# py32f002asop8v1.net
KiCad netlist of a schematic drawn in EasyEDA Pro
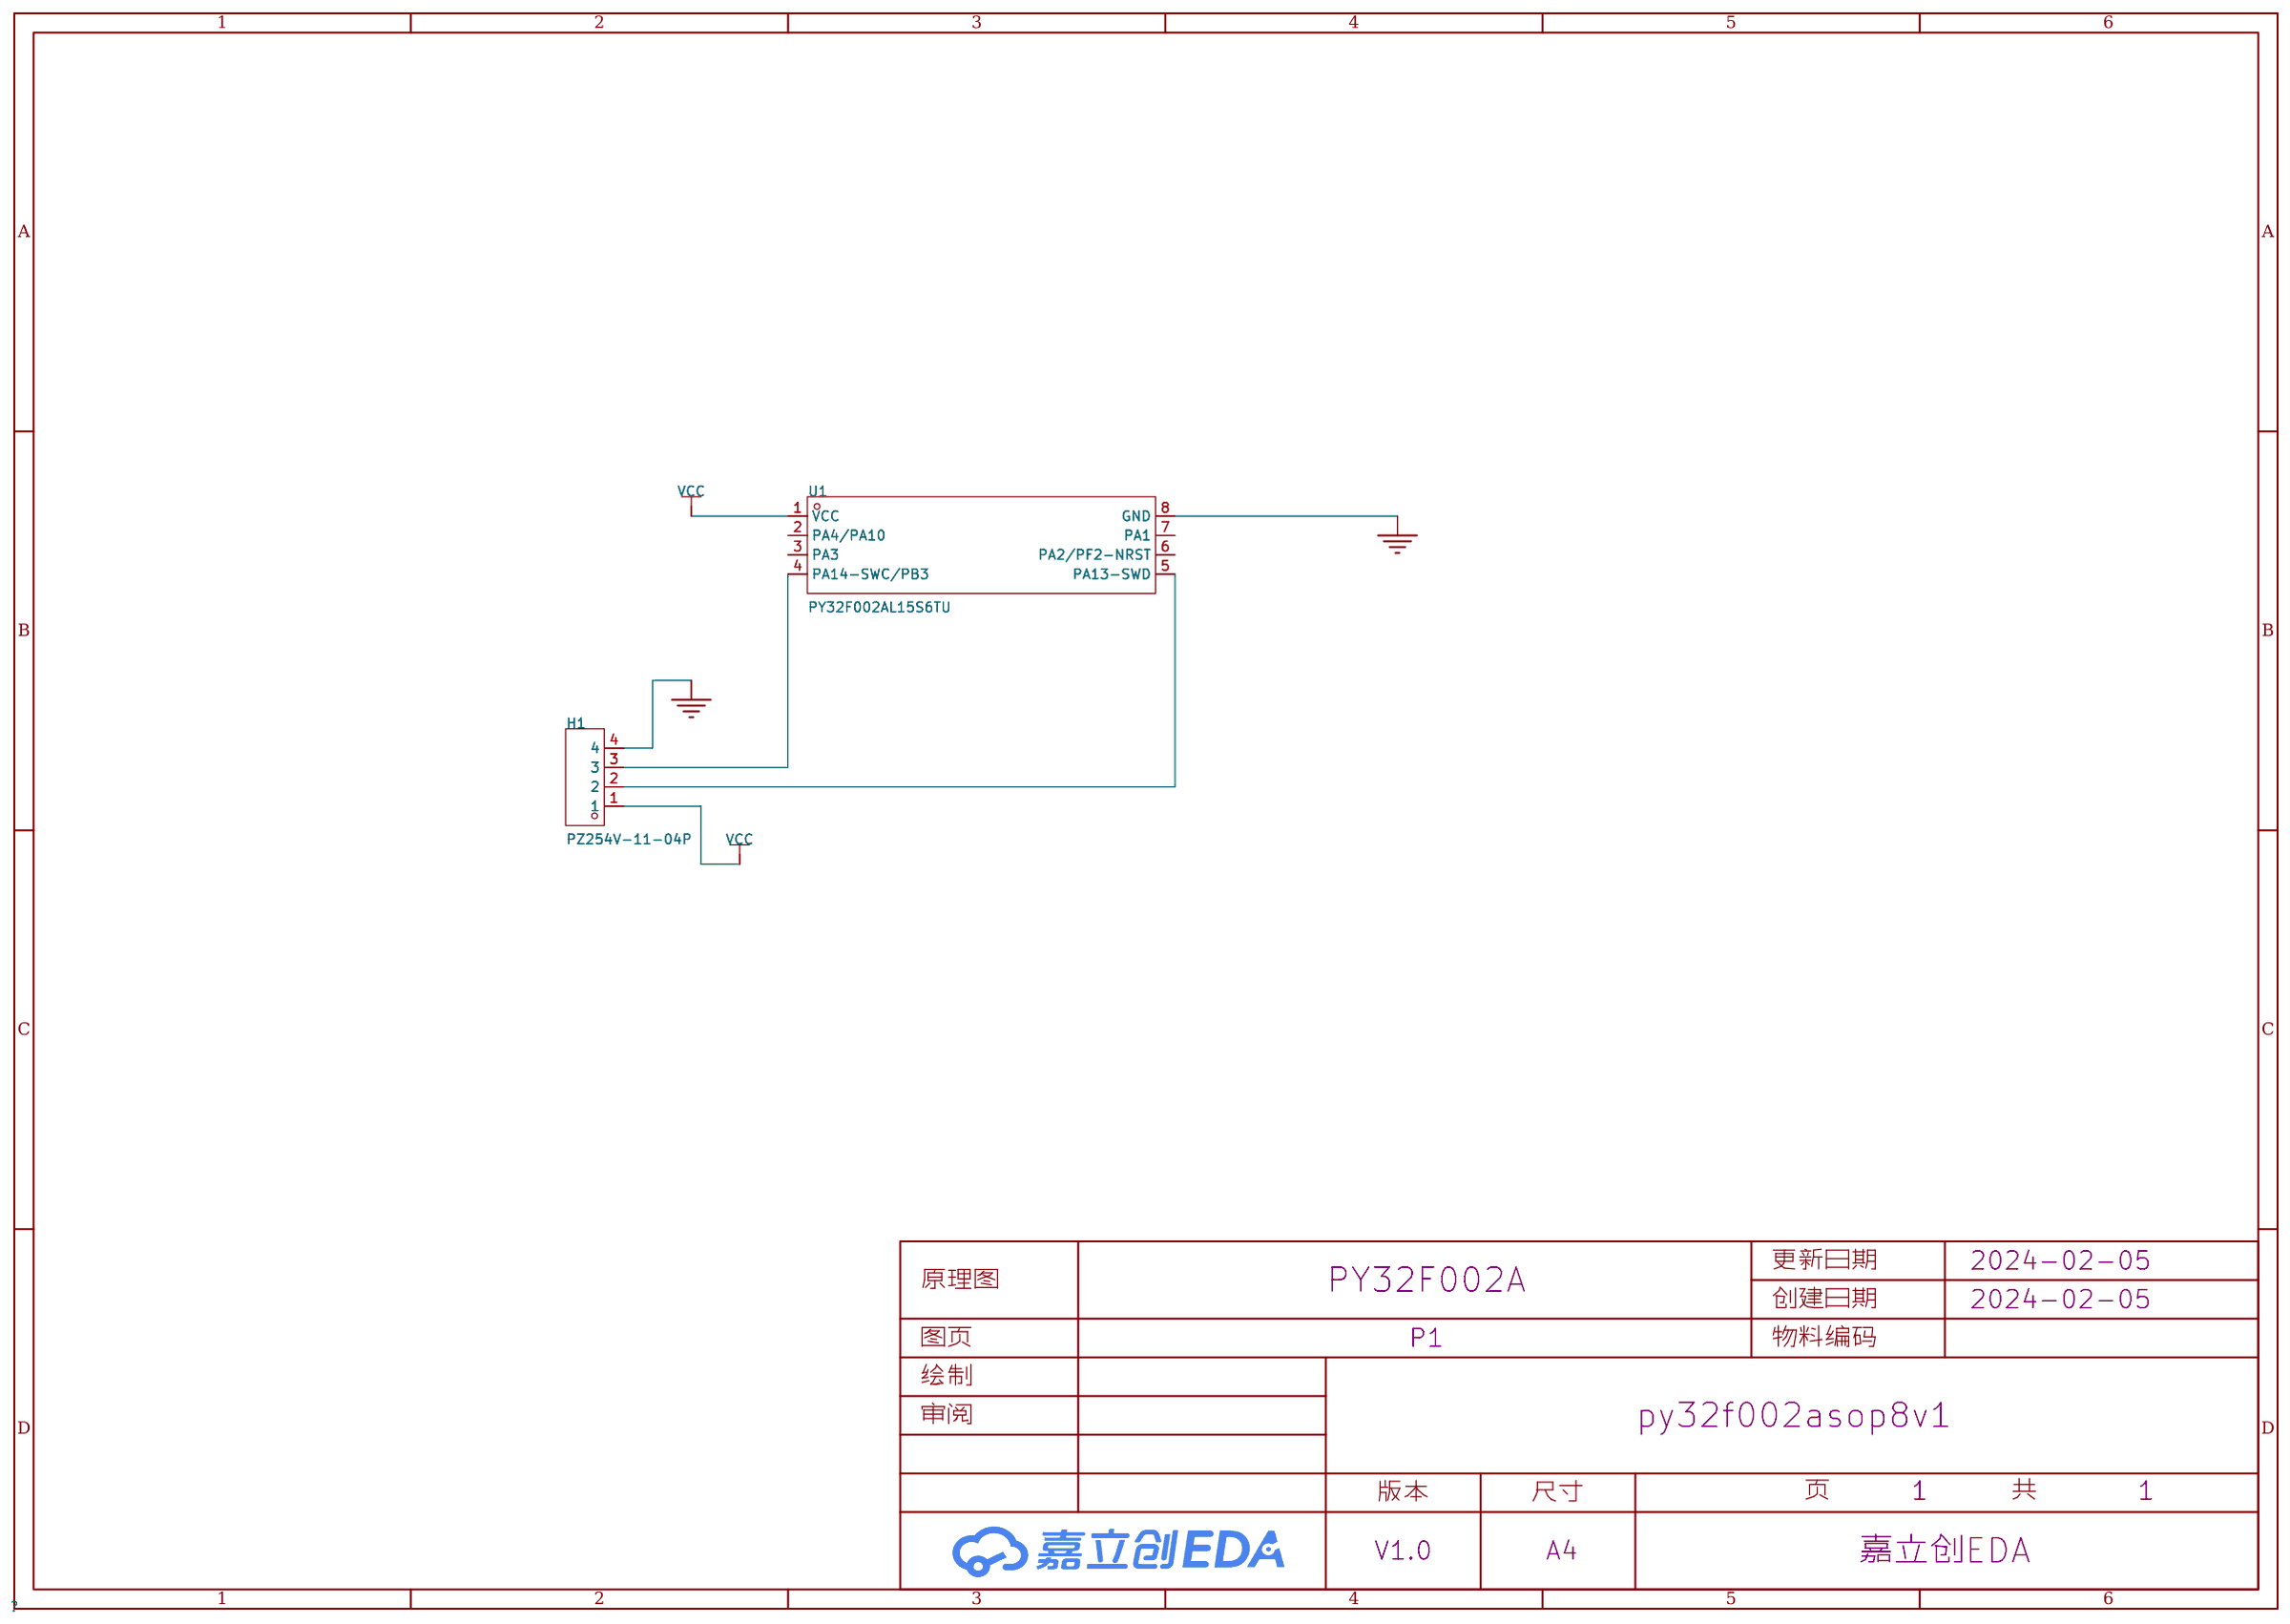
[diagram p0: schematic sheet]

(export (version "E")
  (design (tool "Eeschema 10.0.6"))
  (components
    (comp (ref "H1")
      (value "PZ254V-11-04P")
      (footprint "easyedapro:HDR-TH_4P-P2.54-V-M")
      (fields (field (name "Manufacturer") "XFCN(兴飞)"))
      (libsource (lib "easyedapro") (part "PZ254V-11-04P_C2691448"))
    )
    (comp (ref "U1")
      (value "PY32F002AL15S6TU")
      (footprint "easyedapro:SOP-8_L4.9-W3.9-P1.27-LS6.0-BL-1")
      (description "程序存储容量:20KB;RAM总容量:3KB;工作电压范围:1.7V~5.5V;CPU最大主频:24MHz;程序存储器类型:FLASH;")
      (fields (field (name "Manufacturer") "PUYA(普冉)"))
      (libsource (lib "easyedapro") (part "PY32F002AL15S6TU"))
    )
  )
  (nets
    (net (code "1") (name "GND") (class "Default")
      (node (ref "H1") (pin "4") (pinfunction "4_4") (pintype "unspecified"))
      (node (ref "U1") (pin "8") (pinfunction "GND_8") (pintype "unspecified"))
    )
    (net (code "2") (name "Net-(U1-PA13-SWD)") (class "Default")
      (node (ref "H1") (pin "2") (pinfunction "2_2") (pintype "unspecified"))
      (node (ref "U1") (pin "5") (pinfunction "PA13-SWD_5") (pintype "unspecified"))
    )
    (net (code "3") (name "Net-(U1-PA14-SWC{slash}PB3)") (class "Default")
      (node (ref "H1") (pin "3") (pinfunction "3_3") (pintype "unspecified"))
      (node (ref "U1") (pin "4") (pinfunction "PA14-SWC/PB3_4") (pintype "unspecified"))
    )
    (net (code "4") (name "VCC") (class "Default")
      (node (ref "H1") (pin "1") (pinfunction "1_1") (pintype "unspecified"))
      (node (ref "U1") (pin "1") (pinfunction "VCC_1") (pintype "unspecified"))
    )
    (net (code "5") (name "unconnected-(U1-PA1-Pad7)") (class "Default")
      (node (ref "U1") (pin "7") (pinfunction "PA1_7") (pintype "unspecified"))
    )
    (net (code "6") (name "unconnected-(U1-PA2{slash}PF2-NRST-Pad6)") (class "Default")
      (node (ref "U1") (pin "6") (pinfunction "PA2/PF2-NRST_6") (pintype "unspecified"))
    )
    (net (code "7") (name "unconnected-(U1-PA3-Pad3)") (class "Default")
      (node (ref "U1") (pin "3") (pinfunction "PA3_3") (pintype "unspecified"))
    )
    (net (code "8") (name "unconnected-(U1-PA4{slash}PA10-Pad2)") (class "Default")
      (node (ref "U1") (pin "2") (pinfunction "PA4/PA10_2") (pintype "unspecified"))
    )
  )
)
